# PCB_Cajero_08.net
KiCad netlist of a schematic drawn in EAGLE
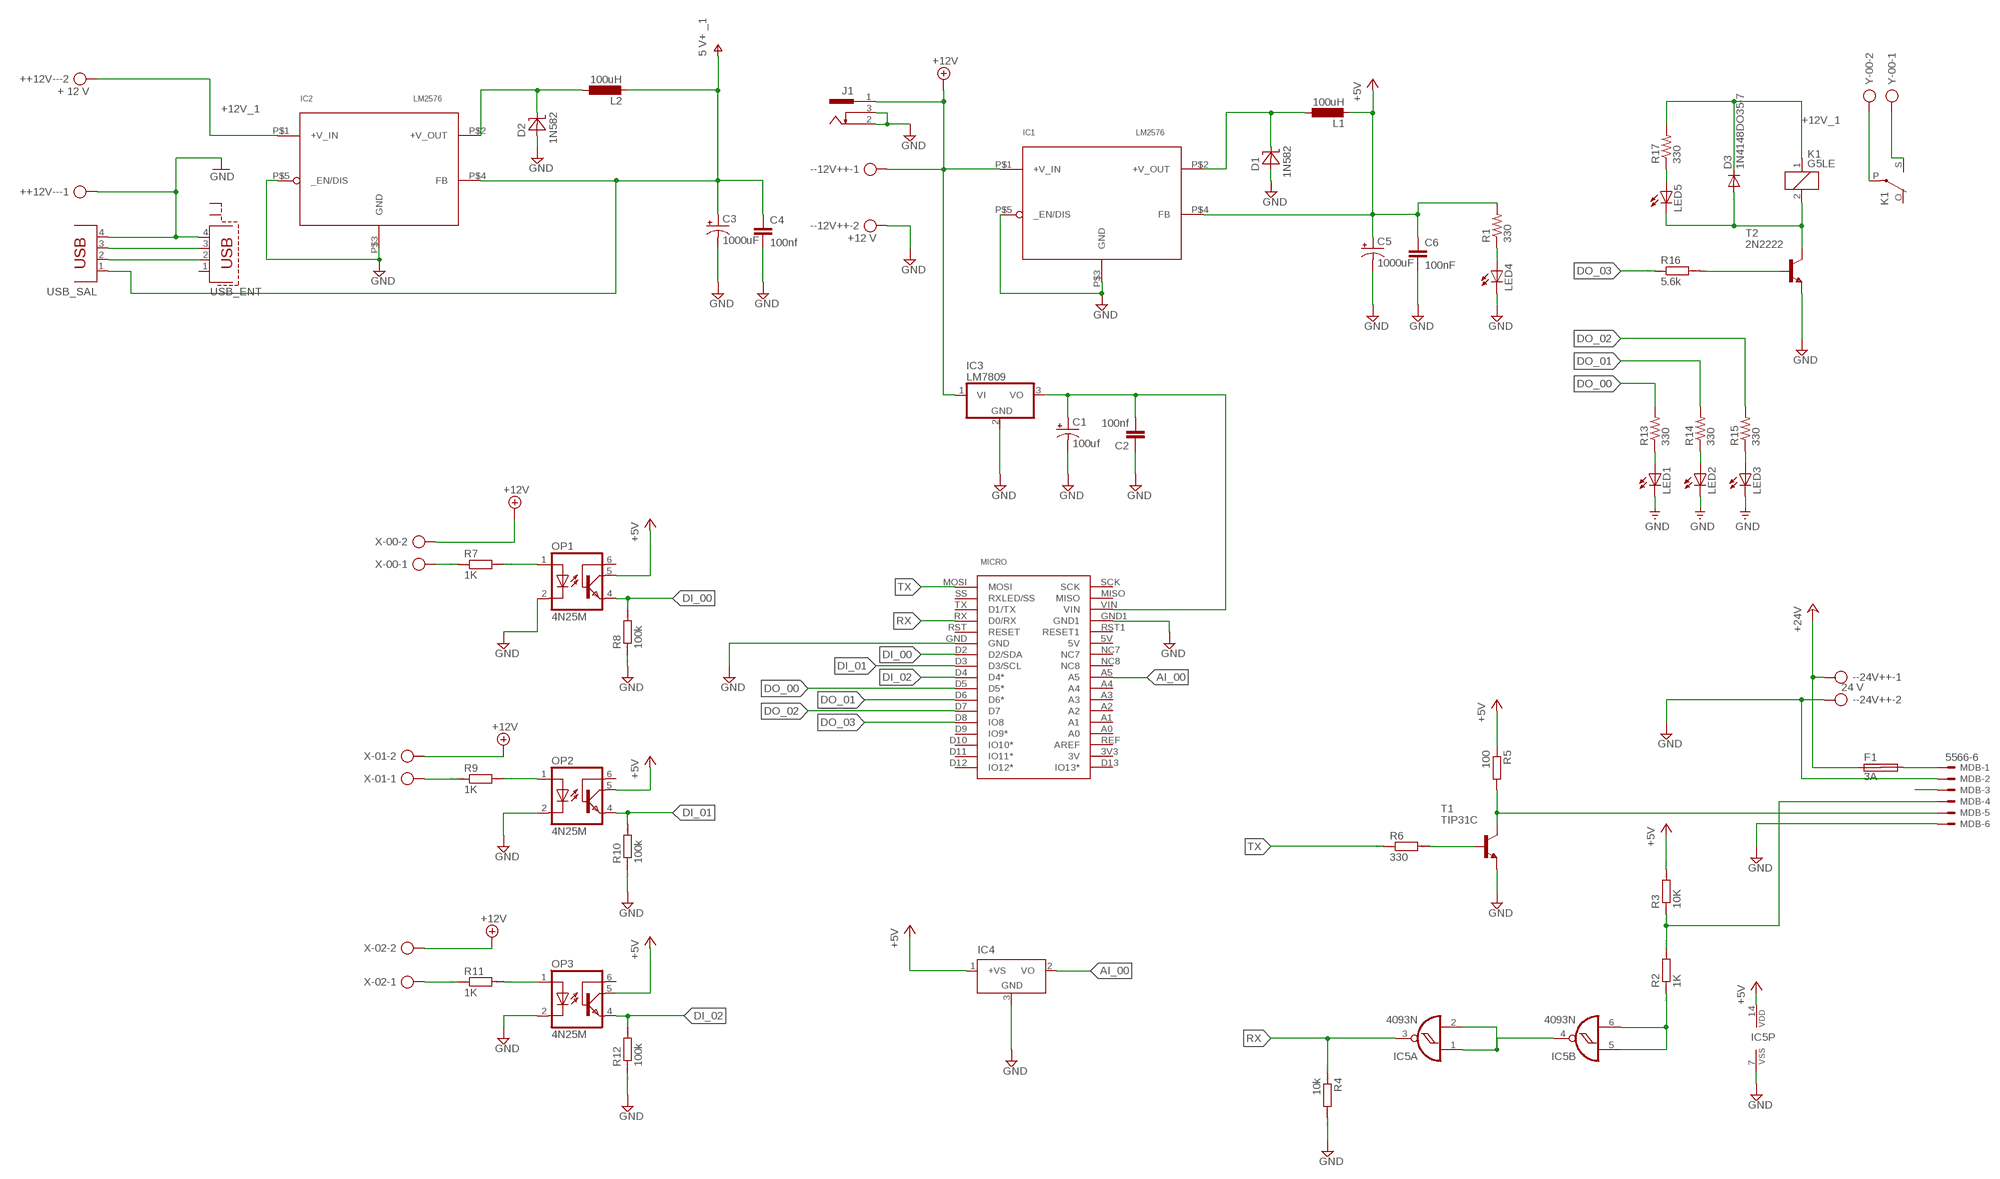
[diagram p0: schematic, sheet 1]

(export (version "E")
  (design (tool "Eeschema 10.0.6"))
  (components
    (comp (ref "++12V--")
      (value "+ 12 V")
      (footprint "eagle-import:AK500_2")
      (libsource (lib "eagle-import") (part "AK500/2"))
    )
    (comp (ref "--12V++")
      (value "+12 V")
      (footprint "eagle-import:AK500_2")
      (libsource (lib "eagle-import") (part "AK500/2"))
    )
    (comp (ref "--24V++")
      (value "24 V")
      (footprint "eagle-import:AK500_2")
      (libsource (lib "eagle-import") (part "AK500/2"))
    )
    (comp (ref "C1")
      (value "100uf")
      (footprint "eagle-import:E2,5-6")
      (libsource (lib "eagle-import") (part "CPOL-USE2.5-6"))
    )
    (comp (ref "C2")
      (value "100nf")
      (footprint "eagle-import:C2.5-3")
      (libsource (lib "eagle-import") (part "C2,5-3"))
    )
    (comp (ref "C3")
      (value "1000uF")
      (footprint "eagle-import:E5-5")
      (libsource (lib "eagle-import") (part "rcl_334_CPOL-USE5-5"))
    )
    (comp (ref "C4")
      (value "100nf")
      (footprint "eagle-import:C2.5-3")
      (libsource (lib "eagle-import") (part "C2,5-3"))
    )
    (comp (ref "C5")
      (value "1000uF")
      (footprint "eagle-import:E5-5")
      (libsource (lib "eagle-import") (part "rcl_334_CPOL-USE5-5"))
    )
    (comp (ref "C6")
      (value "100nF")
      (footprint "eagle-import:C2.5-3")
      (libsource (lib "eagle-import") (part "C2,5-3"))
    )
    (comp (ref "D1")
      (value "1N582")
      (footprint "eagle-import:1N582_")
      (libsource (lib "eagle-import") (part "1N582"))
    )
    (comp (ref "D2")
      (value "1N582")
      (footprint "eagle-import:1N582_")
      (libsource (lib "eagle-import") (part "1N582"))
    )
    (comp (ref "D3")
      (value "1N4148DO35-7")
      (footprint "eagle-import:DO35-7")
      (libsource (lib "eagle-import") (part "1N4148DO35-7"))
    )
    (comp (ref "F1")
      (value "3A")
      (footprint "eagle-import:SHK20L")
      (libsource (lib "eagle-import") (part "SHK20L"))
    )
    (comp (ref "IC1")
      (value "LM2576")
      (footprint "eagle-import:TO220_SEP")
      (libsource (lib "eagle-import") (part "LM2576-T05E"))
    )
    (comp (ref "IC2")
      (value "LM2576")
      (footprint "eagle-import:TO220_SEP")
      (libsource (lib "eagle-import") (part "LM2576-T05E"))
    )
    (comp (ref "IC3")
      (value "LM7809")
      (footprint "eagle-import:TO-220V")
      (libsource (lib "eagle-import") (part "LM7809"))
    )
    (comp (ref "IC4")
      (value "LM35CZ")
      (footprint "eagle-import:TO92")
      (libsource (lib "eagle-import") (part "LM35CZ"))
    )
    (comp (ref "IC5")
      (value "4093N")
      (footprint "eagle-import:DIL14")
      (fields (field (name "SPICEPREFIX") "J"))
      (libsource (lib "eagle-import") (part "4093N"))
    )
    (comp (ref "J1")
      (value "KLDVX-0202-A")
      (footprint "eagle-import:KLDVX-0202-A")
      (libsource (lib "eagle-import") (part "KLDVX-0202-A"))
    )
    (comp (ref "K1")
      (value "G5LE")
      (footprint "eagle-import:G5LE")
      (libsource (lib "eagle-import") (part "G5LE"))
    )
    (comp (ref "L1")
      (value "100uH")
      (footprint "eagle-import:DO3316P")
      (libsource (lib "eagle-import") (part "DO3316P"))
    )
    (comp (ref "L2")
      (value "100uH")
      (footprint "eagle-import:DO3316P")
      (libsource (lib "eagle-import") (part "DO3316P"))
    )
    (comp (ref "LED1")
      (value "LED5MM")
      (footprint "eagle-import:LED5MM")
      (libsource (lib "eagle-import") (part "LED5MM"))
    )
    (comp (ref "LED2")
      (value "LED5MM")
      (footprint "eagle-import:LED5MM")
      (libsource (lib "eagle-import") (part "LED5MM"))
    )
    (comp (ref "LED3")
      (value "LED5MM")
      (footprint "eagle-import:LED5MM")
      (libsource (lib "eagle-import") (part "LED5MM"))
    )
    (comp (ref "LED4")
      (value "LED5MM")
      (footprint "eagle-import:LED5MM")
      (libsource (lib "eagle-import") (part "LED5MM"))
    )
    (comp (ref "LED5")
      (value "LED5MM")
      (footprint "eagle-import:LED5MM")
      (libsource (lib "eagle-import") (part "LED5MM"))
    )
    (comp (ref "MDB")
      (value "5566-6")
      (footprint "eagle-import:5566-6")
      (fields (field (name "MF") "MOLEX") (field (name "MPN") "95566-61002"))
      (libsource (lib "eagle-import") (part "5566-6"))
    )
    (comp (ref "MICRO")
      (value "ARDUINO_MICROFOOTPRINT")
      (footprint "eagle-import:ARDUINO-MICRO")
      (libsource (lib "eagle-import") (part "ARDUINO_MICROFOOTPRINT"))
    )
    (comp (ref "OP1")
      (value "4N25M")
      (footprint "eagle-import:DIL06")
      (fields (field (name "MPN") "4N25-M"))
      (libsource (lib "eagle-import") (part "4N?M25"))
    )
    (comp (ref "OP2")
      (value "4N25M")
      (footprint "eagle-import:DIL06")
      (fields (field (name "MPN") "4N25-M"))
      (libsource (lib "eagle-import") (part "4N?M25"))
    )
    (comp (ref "OP3")
      (value "4N25M")
      (footprint "eagle-import:DIL06")
      (fields (field (name "MPN") "4N25-M"))
      (libsource (lib "eagle-import") (part "4N?M25"))
    )
    (comp (ref "R1")
      (value "330")
      (footprint "eagle-import:0207_7")
      (libsource (lib "eagle-import") (part "R-US_0207/7"))
    )
    (comp (ref "R2")
      (value "1K")
      (footprint "eagle-import:0204_7")
      (libsource (lib "eagle-import") (part "R0204/7"))
    )
    (comp (ref "R3")
      (value "10K")
      (footprint "eagle-import:0204_7")
      (libsource (lib "eagle-import") (part "R0204/7"))
    )
    (comp (ref "R4")
      (value "10k")
      (footprint "eagle-import:0204_7")
      (libsource (lib "eagle-import") (part "R0204/7"))
    )
    (comp (ref "R5")
      (value "100")
      (footprint "eagle-import:0309_10")
      (libsource (lib "eagle-import") (part "R-EU_0309/10"))
    )
    (comp (ref "R6")
      (value "330")
      (footprint "eagle-import:0204_7")
      (libsource (lib "eagle-import") (part "R0204/7"))
    )
    (comp (ref "R7")
      (value "1K")
      (footprint "eagle-import:0204_7")
      (libsource (lib "eagle-import") (part "R0204/7"))
    )
    (comp (ref "R8")
      (value "100k")
      (footprint "eagle-import:0204_7")
      (libsource (lib "eagle-import") (part "R0204/7"))
    )
    (comp (ref "R9")
      (value "1K")
      (footprint "eagle-import:0204_7")
      (libsource (lib "eagle-import") (part "R0204/7"))
    )
    (comp (ref "R10")
      (value "100k")
      (footprint "eagle-import:0204_7")
      (libsource (lib "eagle-import") (part "R0204/7"))
    )
    (comp (ref "R11")
      (value "1K")
      (footprint "eagle-import:0204_7")
      (libsource (lib "eagle-import") (part "R0204/7"))
    )
    (comp (ref "R12")
      (value "100k")
      (footprint "eagle-import:0204_7")
      (libsource (lib "eagle-import") (part "R0204/7"))
    )
    (comp (ref "R13")
      (value "330")
      (footprint "eagle-import:0207_7")
      (libsource (lib "eagle-import") (part "R-US_0207/7"))
    )
    (comp (ref "R14")
      (value "330")
      (footprint "eagle-import:0207_7")
      (libsource (lib "eagle-import") (part "R-US_0207/7"))
    )
    (comp (ref "R15")
      (value "330")
      (footprint "eagle-import:0207_7")
      (libsource (lib "eagle-import") (part "R-US_0207/7"))
    )
    (comp (ref "R16")
      (value "5.6k")
      (footprint "eagle-import:0204_7")
      (libsource (lib "eagle-import") (part "R0204/7"))
    )
    (comp (ref "R17")
      (value "330")
      (footprint "eagle-import:0207_7")
      (libsource (lib "eagle-import") (part "R-US_0207/7"))
    )
    (comp (ref "T1")
      (value "TIP31C")
      (footprint "eagle-import:TO-220V")
      (libsource (lib "eagle-import") (part "TIP31C"))
    )
    (comp (ref "T2")
      (value "2N2222")
      (footprint "eagle-import:TO18")
      (libsource (lib "eagle-import") (part "2N2222"))
    )
    (comp (ref "USB_ENT")
      (value "PN61729-S")
      (footprint "eagle-import:PN61729-S")
      (libsource (lib "eagle-import") (part "PN61729-S"))
    )
    (comp (ref "USB_SAL")
      (value "PN87520")
      (footprint "eagle-import:PN87520")
      (libsource (lib "eagle-import") (part "PN87520"))
    )
    (comp (ref "X-00")
      (value "AK500/2")
      (footprint "eagle-import:AK500_2")
      (libsource (lib "eagle-import") (part "AK500/2"))
    )
    (comp (ref "X-01")
      (value "AK500/2")
      (footprint "eagle-import:AK500_2")
      (libsource (lib "eagle-import") (part "AK500/2"))
    )
    (comp (ref "X-02")
      (value "AK500/2")
      (footprint "eagle-import:AK500_2")
      (libsource (lib "eagle-import") (part "AK500/2"))
    )
    (comp (ref "Y-00")
      (value "AK500/2")
      (footprint "eagle-import:AK500_2")
      (libsource (lib "eagle-import") (part "AK500/2"))
    )
  )
  (nets
    (net (code "1") (name "+5V") (class "Default")
      (node (ref "C5") (pin "+") (pinfunction "+_+") (pintype "passive"))
      (node (ref "C6") (pin "1") (pinfunction "1_1") (pintype "passive"))
      (node (ref "IC1") (pin "P$4") (pinfunction "FB_P$4") (pintype "input"))
      (node (ref "IC4") (pin "1") (pinfunction "+VS_1") (pintype "input"))
      (node (ref "IC5") (pin "14") (pinfunction "VDD_14") (pintype "power_in"))
      (node (ref "L1") (pin "1") (pinfunction "1_1") (pintype "passive"))
      (node (ref "OP1") (pin "5") (pinfunction "COL_5") (pintype "passive"))
      (node (ref "OP2") (pin "5") (pinfunction "COL_5") (pintype "passive"))
      (node (ref "OP3") (pin "5") (pinfunction "COL_5") (pintype "passive"))
      (node (ref "R1") (pin "2") (pinfunction "2_2") (pintype "passive"))
      (node (ref "R3") (pin "2") (pinfunction "2_2") (pintype "passive"))
      (node (ref "R5") (pin "1") (pinfunction "1_1") (pintype "passive"))
    )
    (net (code "2") (name "+12V") (class "Default")
      (node (ref "--12V++") (pin "1") (pinfunction "KL_1") (pintype "passive"))
      (node (ref "IC1") (pin "P$1") (pinfunction "+V_IN_P$1") (pintype "input"))
      (node (ref "IC3") (pin "1") (pinfunction "VI_1") (pintype "input"))
      (node (ref "J1") (pin "1") (pinfunction "1_1") (pintype "passive"))
      (node (ref "X-00") (pin "2") (pinfunction "KL_2") (pintype "passive"))
      (node (ref "X-01") (pin "2") (pinfunction "KL_2") (pintype "passive"))
      (node (ref "X-02") (pin "2") (pinfunction "KL_2") (pintype "passive"))
    )
    (net (code "3") (name "+24V") (class "Default")
      (node (ref "--24V++") (pin "1") (pinfunction "KL_1") (pintype "passive"))
      (node (ref "F1") (pin "1A") (pinfunction "1A_1A") (pintype "passive"))
    )
    (net (code "4") (name "/+12V_1") (class "Default")
      (node (ref "++12V--") (pin "2") (pinfunction "KL_2") (pintype "passive"))
      (node (ref "D3") (pin "C") (pinfunction "C_C") (pintype "passive"))
      (node (ref "IC2") (pin "P$1") (pinfunction "+V_IN_P$1") (pintype "input"))
      (node (ref "K1") (pin "1") (pinfunction "1_1") (pintype "passive"))
      (node (ref "R17") (pin "2") (pinfunction "2_2") (pintype "passive"))
    )
    (net (code "5") (name "5 V+ _1") (class "Default")
      (node (ref "C3") (pin "+") (pinfunction "+_+") (pintype "passive"))
      (node (ref "C4") (pin "1") (pinfunction "1_1") (pintype "passive"))
      (node (ref "IC2") (pin "P$4") (pinfunction "FB_P$4") (pintype "input"))
      (node (ref "L2") (pin "1") (pinfunction "1_1") (pintype "passive"))
      (node (ref "USB_SAL") (pin "1") (pinfunction "1_1") (pintype "passive"))
    )
    (net (code "6") (name "AI_00") (class "Default")
      (node (ref "IC4") (pin "2") (pinfunction "VO_2") (pintype "input"))
      (node (ref "MICRO") (pin "A5") (pinfunction "A5_A5") (pintype "bidirectional"))
    )
    (net (code "7") (name "DI_00") (class "Default")
      (node (ref "MICRO") (pin "D2") (pinfunction "D2/SDA_D2") (pintype "bidirectional"))
      (node (ref "OP1") (pin "4") (pinfunction "EMI_4") (pintype "passive"))
      (node (ref "R8") (pin "2") (pinfunction "2_2") (pintype "passive"))
    )
    (net (code "8") (name "DI_01") (class "Default")
      (node (ref "MICRO") (pin "D3") (pinfunction "D3/SCL_D3") (pintype "bidirectional"))
      (node (ref "OP2") (pin "4") (pinfunction "EMI_4") (pintype "passive"))
      (node (ref "R10") (pin "2") (pinfunction "2_2") (pintype "passive"))
    )
    (net (code "9") (name "DI_02") (class "Default")
      (node (ref "MICRO") (pin "D4") (pinfunction "D4*_D4") (pintype "bidirectional"))
      (node (ref "OP3") (pin "4") (pinfunction "EMI_4") (pintype "passive"))
      (node (ref "R12") (pin "2") (pinfunction "2_2") (pintype "passive"))
    )
    (net (code "10") (name "DO_00") (class "Default")
      (node (ref "MICRO") (pin "D5") (pinfunction "D5*_D5") (pintype "bidirectional"))
      (node (ref "R13") (pin "2") (pinfunction "2_2") (pintype "passive"))
    )
    (net (code "11") (name "DO_01") (class "Default")
      (node (ref "MICRO") (pin "D6") (pinfunction "D6*_D6") (pintype "bidirectional"))
      (node (ref "R14") (pin "2") (pinfunction "2_2") (pintype "passive"))
    )
    (net (code "12") (name "DO_02") (class "Default")
      (node (ref "MICRO") (pin "D7") (pinfunction "D7_D7") (pintype "bidirectional"))
      (node (ref "R15") (pin "2") (pinfunction "2_2") (pintype "passive"))
    )
    (net (code "13") (name "DO_03") (class "Default")
      (node (ref "MICRO") (pin "D8") (pinfunction "IO8_D8") (pintype "bidirectional"))
      (node (ref "R16") (pin "1") (pinfunction "1_1") (pintype "passive"))
    )
    (net (code "14") (name "GND") (class "Default")
      (node (ref "++12V--") (pin "1") (pinfunction "KL_1") (pintype "passive"))
      (node (ref "--12V++") (pin "2") (pinfunction "KL_2") (pintype "passive"))
      (node (ref "--24V++") (pin "2") (pinfunction "KL_2") (pintype "passive"))
      (node (ref "C1") (pin "-") (pinfunction "-_-") (pintype "passive"))
      (node (ref "C2") (pin "1") (pinfunction "1_1") (pintype "passive"))
      (node (ref "C3") (pin "-") (pinfunction "-_-") (pintype "passive"))
      (node (ref "C4") (pin "2") (pinfunction "2_2") (pintype "passive"))
      (node (ref "C5") (pin "-") (pinfunction "-_-") (pintype "passive"))
      (node (ref "C6") (pin "2") (pinfunction "2_2") (pintype "passive"))
      (node (ref "D1") (pin "A") (pinfunction "A_A") (pintype "passive"))
      (node (ref "D2") (pin "A") (pinfunction "A_A") (pintype "passive"))
      (node (ref "IC1") (pin "P$3") (pinfunction "GND_P$3") (pintype "power_in"))
      (node (ref "IC1") (pin "P$5") (pinfunction "_EN/DIS_P$5") (pintype "input"))
      (node (ref "IC2") (pin "P$3") (pinfunction "GND_P$3") (pintype "power_in"))
      (node (ref "IC2") (pin "P$5") (pinfunction "_EN/DIS_P$5") (pintype "input"))
      (node (ref "IC3") (pin "2") (pinfunction "GND_2") (pintype "passive"))
      (node (ref "IC4") (pin "3") (pinfunction "GND_3") (pintype "power_in"))
      (node (ref "IC5") (pin "7") (pinfunction "VSS_7") (pintype "power_in"))
      (node (ref "J1") (pin "2") (pinfunction "2_2") (pintype "passive"))
      (node (ref "J1") (pin "3") (pinfunction "3_3") (pintype "passive"))
      (node (ref "LED1") (pin "K") (pinfunction "C_K") (pintype "passive"))
      (node (ref "LED2") (pin "K") (pinfunction "C_K") (pintype "passive"))
      (node (ref "LED3") (pin "K") (pinfunction "C_K") (pintype "passive"))
      (node (ref "LED4") (pin "K") (pinfunction "C_K") (pintype "passive"))
      (node (ref "MDB") (pin "2") (pinfunction "S_2") (pintype "passive"))
      (node (ref "MDB") (pin "6") (pinfunction "S_6") (pintype "passive"))
      (node (ref "MICRO") (pin "GND") (pinfunction "GND_GND") (pintype "bidirectional"))
      (node (ref "MICRO") (pin "GND1") (pinfunction "GND1_GND1") (pintype "bidirectional"))
      (node (ref "OP1") (pin "2") (pinfunction "C_2") (pintype "passive"))
      (node (ref "OP2") (pin "2") (pinfunction "C_2") (pintype "passive"))
      (node (ref "OP3") (pin "2") (pinfunction "C_2") (pintype "passive"))
      (node (ref "R10") (pin "1") (pinfunction "1_1") (pintype "passive"))
      (node (ref "R12") (pin "1") (pinfunction "1_1") (pintype "passive"))
      (node (ref "R4") (pin "2") (pinfunction "2_2") (pintype "passive"))
      (node (ref "R8") (pin "1") (pinfunction "1_1") (pintype "passive"))
      (node (ref "T1") (pin "3") (pinfunction "E_3") (pintype "passive"))
      (node (ref "T2") (pin "1") (pinfunction "E_1") (pintype "passive"))
      (node (ref "USB_ENT") (pin "4") (pinfunction "4_4") (pintype "passive"))
      (node (ref "USB_SAL") (pin "4") (pinfunction "4_4") (pintype "passive"))
    )
    (net (code "15") (name "Net-(IC1-+V_OUT)") (class "Default")
      (node (ref "D1") (pin "C") (pinfunction "C_C") (pintype "passive"))
      (node (ref "IC1") (pin "P$2") (pinfunction "+V_OUT_P$2") (pintype "output"))
      (node (ref "L1") (pin "2") (pinfunction "2_2") (pintype "passive"))
    )
    (net (code "16") (name "Net-(IC2-+V_OUT)") (class "Default")
      (node (ref "D2") (pin "C") (pinfunction "C_C") (pintype "passive"))
      (node (ref "IC2") (pin "P$2") (pinfunction "+V_OUT_P$2") (pintype "output"))
      (node (ref "L2") (pin "2") (pinfunction "2_2") (pintype "passive"))
    )
    (net (code "17") (name "Net-(IC3-VO)") (class "Default")
      (node (ref "C1") (pin "+") (pinfunction "+_+") (pintype "passive"))
      (node (ref "C2") (pin "2") (pinfunction "2_2") (pintype "passive"))
      (node (ref "IC3") (pin "3") (pinfunction "VO_3") (pintype "passive"))
      (node (ref "MICRO") (pin "VIN") (pinfunction "VIN_VIN") (pintype "bidirectional"))
    )
    (net (code "18") (name "Net-(IC5A-I0)") (class "Default")
      (node (ref "IC5") (pin "1") (pinfunction "I0_1") (pintype "input"))
      (node (ref "IC5") (pin "2") (pinfunction "I1_2") (pintype "input"))
      (node (ref "IC5") (pin "4") (pinfunction "O_4") (pintype "output"))
    )
    (net (code "19") (name "Net-(IC5B-I0)") (class "Default")
      (node (ref "IC5") (pin "5") (pinfunction "I0_5") (pintype "input"))
      (node (ref "IC5") (pin "6") (pinfunction "I1_6") (pintype "input"))
      (node (ref "R2") (pin "1") (pinfunction "1_1") (pintype "passive"))
    )
    (net (code "20") (name "Net-(LED1-PadA)") (class "Default")
      (node (ref "LED1") (pin "A") (pinfunction "A_A") (pintype "passive"))
      (node (ref "R13") (pin "1") (pinfunction "1_1") (pintype "passive"))
    )
    (net (code "21") (name "Net-(LED2-PadA)") (class "Default")
      (node (ref "LED2") (pin "A") (pinfunction "A_A") (pintype "passive"))
      (node (ref "R14") (pin "1") (pinfunction "1_1") (pintype "passive"))
    )
    (net (code "22") (name "Net-(LED3-PadA)") (class "Default")
      (node (ref "LED3") (pin "A") (pinfunction "A_A") (pintype "passive"))
      (node (ref "R15") (pin "1") (pinfunction "1_1") (pintype "passive"))
    )
    (net (code "23") (name "Net-(LED4-PadA)") (class "Default")
      (node (ref "LED4") (pin "A") (pinfunction "A_A") (pintype "passive"))
      (node (ref "R1") (pin "1") (pinfunction "1_1") (pintype "passive"))
    )
    (net (code "24") (name "Net-(LED5-C)") (class "Default")
      (node (ref "D3") (pin "A") (pinfunction "A_A") (pintype "passive"))
      (node (ref "K1") (pin "2") (pinfunction "2_2") (pintype "passive"))
      (node (ref "LED5") (pin "K") (pinfunction "C_K") (pintype "passive"))
      (node (ref "T2") (pin "3") (pinfunction "C_3") (pintype "passive"))
    )
    (net (code "25") (name "Net-(LED5-PadA)") (class "Default")
      (node (ref "LED5") (pin "A") (pinfunction "A_A") (pintype "passive"))
      (node (ref "R17") (pin "1") (pinfunction "1_1") (pintype "passive"))
    )
    (net (code "26") (name "Net-(MDBA-S)") (class "Default")
      (node (ref "F1") (pin "2A") (pinfunction "2A_2A") (pintype "passive"))
      (node (ref "MDB") (pin "1") (pinfunction "S_1") (pintype "passive"))
    )
    (net (code "27") (name "Net-(MDBD-S)") (class "Default")
      (node (ref "MDB") (pin "4") (pinfunction "S_4") (pintype "passive"))
      (node (ref "R2") (pin "2") (pinfunction "2_2") (pintype "passive"))
      (node (ref "R3") (pin "1") (pinfunction "1_1") (pintype "passive"))
    )
    (net (code "28") (name "Net-(MDBE-S)") (class "Default")
      (node (ref "MDB") (pin "5") (pinfunction "S_5") (pintype "passive"))
      (node (ref "R5") (pin "2") (pinfunction "2_2") (pintype "passive"))
      (node (ref "T1") (pin "2") (pinfunction "C_2") (pintype "passive"))
    )
    (net (code "29") (name "Net-(OP1-A)") (class "Default")
      (node (ref "OP1") (pin "1") (pinfunction "A_1") (pintype "passive"))
      (node (ref "R7") (pin "2") (pinfunction "2_2") (pintype "passive"))
    )
    (net (code "30") (name "Net-(OP2-A)") (class "Default")
      (node (ref "OP2") (pin "1") (pinfunction "A_1") (pintype "passive"))
      (node (ref "R9") (pin "2") (pinfunction "2_2") (pintype "passive"))
    )
    (net (code "31") (name "Net-(OP3-A)") (class "Default")
      (node (ref "OP3") (pin "1") (pinfunction "A_1") (pintype "passive"))
      (node (ref "R11") (pin "2") (pinfunction "2_2") (pintype "passive"))
    )
    (net (code "32") (name "Net-(T1-B)") (class "Default")
      (node (ref "R6") (pin "2") (pinfunction "2_2") (pintype "passive"))
      (node (ref "T1") (pin "1") (pinfunction "B_1") (pintype "passive"))
    )
    (net (code "33") (name "Net-(T2-B)") (class "Default")
      (node (ref "R16") (pin "2") (pinfunction "2_2") (pintype "passive"))
      (node (ref "T2") (pin "2") (pinfunction "B_2") (pintype "passive"))
    )
    (net (code "34") (name "Net-(USB_ENT-Pad2)") (class "Default")
      (node (ref "USB_ENT") (pin "2") (pinfunction "2_2") (pintype "passive"))
      (node (ref "USB_SAL") (pin "2") (pinfunction "2_2") (pintype "passive"))
    )
    (net (code "35") (name "Net-(USB_ENT-Pad3)") (class "Default")
      (node (ref "USB_ENT") (pin "3") (pinfunction "3_3") (pintype "passive"))
      (node (ref "USB_SAL") (pin "3") (pinfunction "3_3") (pintype "passive"))
    )
    (net (code "36") (name "Net-(X-00A-KL)") (class "Default")
      (node (ref "R7") (pin "1") (pinfunction "1_1") (pintype "passive"))
      (node (ref "X-00") (pin "1") (pinfunction "KL_1") (pintype "passive"))
    )
    (net (code "37") (name "Net-(X-01A-KL)") (class "Default")
      (node (ref "R9") (pin "1") (pinfunction "1_1") (pintype "passive"))
      (node (ref "X-01") (pin "1") (pinfunction "KL_1") (pintype "passive"))
    )
    (net (code "38") (name "Net-(X-02A-KL)") (class "Default")
      (node (ref "R11") (pin "1") (pinfunction "1_1") (pintype "passive"))
      (node (ref "X-02") (pin "1") (pinfunction "KL_1") (pintype "passive"))
    )
    (net (code "39") (name "Net-(Y-00A-KL)") (class "Default")
      (node (ref "K1") (pin "S") (pinfunction "S_S") (pintype "passive"))
      (node (ref "Y-00") (pin "1") (pinfunction "KL_1") (pintype "passive"))
    )
    (net (code "40") (name "Net-(Y-00B-KL)") (class "Default")
      (node (ref "K1") (pin "P") (pinfunction "P_P") (pintype "passive"))
      (node (ref "Y-00") (pin "2") (pinfunction "KL_2") (pintype "passive"))
    )
    (net (code "41") (name "RX") (class "Default")
      (node (ref "IC5") (pin "3") (pinfunction "O_3") (pintype "output"))
      (node (ref "MICRO") (pin "RX") (pinfunction "D0/RX_RX") (pintype "bidirectional"))
      (node (ref "R4") (pin "1") (pinfunction "1_1") (pintype "passive"))
    )
    (net (code "42") (name "TX") (class "Default")
      (node (ref "MICRO") (pin "MOSI") (pinfunction "MOSI_MOSI") (pintype "bidirectional"))
      (node (ref "R6") (pin "1") (pinfunction "1_1") (pintype "passive"))
    )
    (net (code "43") (name "unconnected-(F1-Pad1B)") (class "Default")
      (node (ref "F1") (pin "1B") (pinfunction "1B_1B") (pintype "passive"))
    )
    (net (code "44") (name "unconnected-(F1-Pad2B)") (class "Default")
      (node (ref "F1") (pin "2B") (pinfunction "2B_2B") (pintype "passive"))
    )
    (net (code "45") (name "unconnected-(J1-1-Pad1@1)") (class "Default")
      (node (ref "J1") (pin "1@1") (pinfunction "1_1@1") (pintype "passive"))
    )
    (net (code "46") (name "unconnected-(J1-2-Pad2@1)") (class "Default")
      (node (ref "J1") (pin "2@1") (pinfunction "2_2@1") (pintype "passive"))
    )
    (net (code "47") (name "unconnected-(J1-3-Pad3@1)") (class "Default")
      (node (ref "J1") (pin "3@1") (pinfunction "3_3@1") (pintype "passive"))
    )
    (net (code "48") (name "unconnected-(K1-PadO)") (class "Default")
      (node (ref "K1") (pin "O") (pinfunction "O_O") (pintype "passive"))
    )
    (net (code "49") (name "unconnected-(MDBC-S-Pad3)") (class "Default")
      (node (ref "MDB") (pin "3") (pinfunction "S_3") (pintype "passive"))
    )
    (net (code "50") (name "unconnected-(MICRO-3V-Pad3V3)") (class "Default")
      (node (ref "MICRO") (pin "3V3") (pinfunction "3V_3V3") (pintype "bidirectional"))
    )
    (net (code "51") (name "unconnected-(MICRO-AREF-PadREF)") (class "Default")
      (node (ref "MICRO") (pin "REF") (pinfunction "AREF_REF") (pintype "bidirectional"))
    )
    (net (code "52") (name "unconnected-(MICRO-D1{slash}TX-PadTX)") (class "Default")
      (node (ref "MICRO") (pin "TX") (pinfunction "D1/TX_TX") (pintype "bidirectional"))
    )
    (net (code "53") (name "unconnected-(MICRO-IO9*-PadD9)") (class "Default")
      (node (ref "MICRO") (pin "D9") (pinfunction "IO9*_D9") (pintype "bidirectional"))
    )
    (net (code "54") (name "unconnected-(MICRO-IO10*-PadD10)") (class "Default")
      (node (ref "MICRO") (pin "D10") (pinfunction "IO10*_D10") (pintype "bidirectional"))
    )
    (net (code "55") (name "unconnected-(MICRO-IO11*-PadD11)") (class "Default")
      (node (ref "MICRO") (pin "D11") (pinfunction "IO11*_D11") (pintype "bidirectional"))
    )
    (net (code "56") (name "unconnected-(MICRO-IO12*-PadD12)") (class "Default")
      (node (ref "MICRO") (pin "D12") (pinfunction "IO12*_D12") (pintype "bidirectional"))
    )
    (net (code "57") (name "unconnected-(MICRO-IO13*-PadD13)") (class "Default")
      (node (ref "MICRO") (pin "D13") (pinfunction "IO13*_D13") (pintype "bidirectional"))
    )
    (net (code "58") (name "unconnected-(MICRO-Pad5V)") (class "Default")
      (node (ref "MICRO") (pin "5V") (pinfunction "5V_5V") (pintype "bidirectional"))
    )
    (net (code "59") (name "unconnected-(MICRO-PadA0)") (class "Default")
      (node (ref "MICRO") (pin "A0") (pinfunction "A0_A0") (pintype "bidirectional"))
    )
    (net (code "60") (name "unconnected-(MICRO-PadA1)") (class "Default")
      (node (ref "MICRO") (pin "A1") (pinfunction "A1_A1") (pintype "bidirectional"))
    )
    (net (code "61") (name "unconnected-(MICRO-PadA2)") (class "Default")
      (node (ref "MICRO") (pin "A2") (pinfunction "A2_A2") (pintype "bidirectional"))
    )
    (net (code "62") (name "unconnected-(MICRO-PadA3)") (class "Default")
      (node (ref "MICRO") (pin "A3") (pinfunction "A3_A3") (pintype "bidirectional"))
    )
    (net (code "63") (name "unconnected-(MICRO-PadA4)") (class "Default")
      (node (ref "MICRO") (pin "A4") (pinfunction "A4_A4") (pintype "bidirectional"))
    )
    (net (code "64") (name "unconnected-(MICRO-PadMISO)") (class "Default")
      (node (ref "MICRO") (pin "MISO") (pinfunction "MISO_MISO") (pintype "bidirectional"))
    )
    (net (code "65") (name "unconnected-(MICRO-PadNC7)") (class "Default")
      (node (ref "MICRO") (pin "NC7") (pinfunction "NC7_NC7") (pintype "bidirectional"))
    )
    (net (code "66") (name "unconnected-(MICRO-PadNC8)") (class "Default")
      (node (ref "MICRO") (pin "NC8") (pinfunction "NC8_NC8") (pintype "bidirectional"))
    )
    (net (code "67") (name "unconnected-(MICRO-PadSCK)") (class "Default")
      (node (ref "MICRO") (pin "SCK") (pinfunction "SCK_SCK") (pintype "bidirectional"))
    )
    (net (code "68") (name "unconnected-(MICRO-RESET-PadRST)") (class "Default")
      (node (ref "MICRO") (pin "RST") (pinfunction "RESET_RST") (pintype "bidirectional"))
    )
    (net (code "69") (name "unconnected-(MICRO-RESET1-PadRST1)") (class "Default")
      (node (ref "MICRO") (pin "RST1") (pinfunction "RESET1_RST1") (pintype "bidirectional"))
    )
    (net (code "70") (name "unconnected-(MICRO-RXLED{slash}SS-PadSS)") (class "Default")
      (node (ref "MICRO") (pin "SS") (pinfunction "RXLED/SS_SS") (pintype "bidirectional"))
    )
    (net (code "71") (name "unconnected-(OP1-BAS-Pad6)") (class "Default")
      (node (ref "OP1") (pin "6") (pinfunction "BAS_6") (pintype "passive"))
    )
    (net (code "72") (name "unconnected-(OP2-BAS-Pad6)") (class "Default")
      (node (ref "OP2") (pin "6") (pinfunction "BAS_6") (pintype "passive"))
    )
    (net (code "73") (name "unconnected-(OP3-BAS-Pad6)") (class "Default")
      (node (ref "OP3") (pin "6") (pinfunction "BAS_6") (pintype "passive"))
    )
    (net (code "74") (name "unconnected-(USB_ENT-Pad1)") (class "Default")
      (node (ref "USB_ENT") (pin "1") (pinfunction "1_1") (pintype "passive"))
    )
    (net (code "75") (name "unconnected-(USB_ENT-PadS1)") (class "Default")
      (node (ref "USB_ENT") (pin "S1") (pinfunction "S1_S1") (pintype "passive"))
    )
    (net (code "76") (name "unconnected-(USB_ENT-PadS2)") (class "Default")
      (node (ref "USB_ENT") (pin "S2") (pinfunction "S2_S2") (pintype "passive"))
    )
  )
)
